# Lesson_06_2.net
KiCad netlist of a schematic drawn in Altium Designer
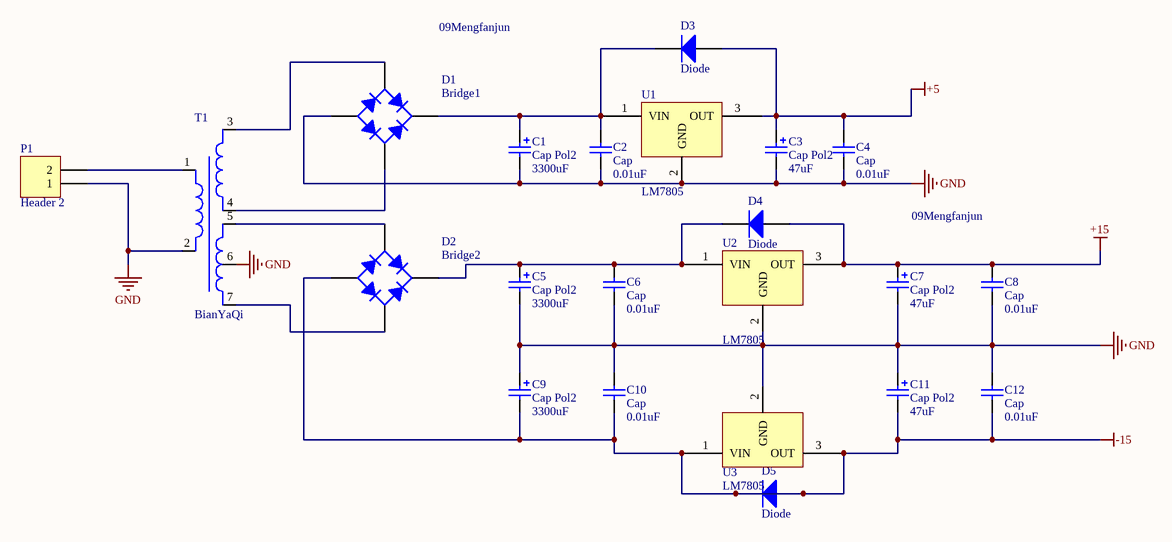
[diagram p0: Lesson_06_2.SchDoc]

(export (version "E")
  (design (tool "Eeschema 10.0.6"))
  (components
    (comp (ref "C1")
      (value "Cap Pol2")
      (footprint "POLAR0.8")
      (description "Polarized Capacitor (Axial)")
      (fields (field (name "ALTIUM_VALUE") "3300uF") (field (name "PUBLISHER") "Altium Limited"))
      (libsource (lib "Miscellaneous Devices") (part "Cap Pol2"))
    )
    (comp (ref "C2")
      (value "Cap")
      (footprint "RAD-0.3")
      (description "Capacitor")
      (fields (field (name "ALTIUM_VALUE") "0.01uF") (field (name "PUBLISHER") "Altium Limited"))
      (libsource (lib "Miscellaneous Devices") (part "Cap"))
    )
    (comp (ref "C3")
      (value "Cap Pol2")
      (footprint "POLAR0.8")
      (description "Polarized Capacitor (Axial)")
      (fields (field (name "ALTIUM_VALUE") "47uF") (field (name "PUBLISHER") "Altium Limited"))
      (libsource (lib "Miscellaneous Devices") (part "Cap Pol2"))
    )
    (comp (ref "C4")
      (value "Cap")
      (footprint "RAD-0.3")
      (description "Capacitor")
      (fields (field (name "ALTIUM_VALUE") "0.01uF") (field (name "PUBLISHER") "Altium Limited"))
      (libsource (lib "Miscellaneous Devices") (part "Cap"))
    )
    (comp (ref "C5")
      (value "Cap Pol2")
      (footprint "POLAR0.8")
      (description "Polarized Capacitor (Axial)")
      (fields (field (name "ALTIUM_VALUE") "3300uF") (field (name "PUBLISHER") "Altium Limited"))
      (libsource (lib "Miscellaneous Devices") (part "Cap Pol2"))
    )
    (comp (ref "C6")
      (value "Cap")
      (footprint "RAD-0.3")
      (description "Capacitor")
      (fields (field (name "ALTIUM_VALUE") "0.01uF") (field (name "PUBLISHER") "Altium Limited"))
      (libsource (lib "Miscellaneous Devices") (part "Cap"))
    )
    (comp (ref "C7")
      (value "Cap Pol2")
      (footprint "POLAR0.8")
      (description "Polarized Capacitor (Axial)")
      (fields (field (name "ALTIUM_VALUE") "47uF") (field (name "PUBLISHER") "Altium Limited"))
      (libsource (lib "Miscellaneous Devices") (part "Cap Pol2"))
    )
    (comp (ref "C8")
      (value "Cap")
      (footprint "RAD-0.3")
      (description "Capacitor")
      (fields (field (name "ALTIUM_VALUE") "0.01uF") (field (name "PUBLISHER") "Altium Limited"))
      (libsource (lib "Miscellaneous Devices") (part "Cap"))
    )
    (comp (ref "C9")
      (value "Cap Pol2")
      (footprint "POLAR0.8")
      (description "Polarized Capacitor (Axial)")
      (fields (field (name "ALTIUM_VALUE") "3300uF") (field (name "PUBLISHER") "Altium Limited"))
      (libsource (lib "Miscellaneous Devices") (part "Cap Pol2"))
    )
    (comp (ref "C10")
      (value "Cap")
      (footprint "RAD-0.3")
      (description "Capacitor")
      (fields (field (name "ALTIUM_VALUE") "0.01uF") (field (name "PUBLISHER") "Altium Limited"))
      (libsource (lib "Miscellaneous Devices") (part "Cap"))
    )
    (comp (ref "C11")
      (value "Cap Pol2")
      (footprint "POLAR0.8")
      (description "Polarized Capacitor (Axial)")
      (fields (field (name "ALTIUM_VALUE") "47uF") (field (name "PUBLISHER") "Altium Limited"))
      (libsource (lib "Miscellaneous Devices") (part "Cap Pol2"))
    )
    (comp (ref "C12")
      (value "Cap")
      (footprint "RAD-0.3")
      (description "Capacitor")
      (fields (field (name "ALTIUM_VALUE") "0.01uF") (field (name "PUBLISHER") "Altium Limited"))
      (libsource (lib "Miscellaneous Devices") (part "Cap"))
    )
    (comp (ref "D1")
      (value "Bridge1")
      (footprint "D-38")
      (description "Full Wave Diode Bridge")
      (fields (field (name "PUBLISHER") "Altium Limited"))
      (libsource (lib "Miscellaneous Devices") (part "Bridge1"))
    )
    (comp (ref "D2")
      (value "Bridge2")
      (footprint "D-38")
      (description "Full Wave Diode Bridge")
      (fields (field (name "PUBLISHER") "Altium Limited"))
      (libsource (lib "Miscellaneous Devices") (part "Bridge1"))
    )
    (comp (ref "D3")
      (value "Diode")
      (footprint "SMC")
      (description "Default Diode")
      (fields (field (name "PUBLISHER") "Altium Limited"))
      (libsource (lib "Miscellaneous Devices") (part "Diode"))
    )
    (comp (ref "D4")
      (value "Diode")
      (footprint "SMC")
      (description "Default Diode")
      (fields (field (name "PUBLISHER") "Altium Limited"))
      (libsource (lib "Miscellaneous Devices") (part "Diode"))
    )
    (comp (ref "D5")
      (value "Diode")
      (footprint "SMC")
      (description "Default Diode")
      (fields (field (name "PUBLISHER") "Altium Limited"))
      (libsource (lib "Miscellaneous Devices") (part "Diode"))
    )
    (comp (ref "P1")
      (value "Header 2")
      (footprint "HDR1X2")
      (description "Header, 2-Pin")
      (fields (field (name "PUBLISHER") "Altium Limited"))
      (libsource (lib "Miscellaneous Connectors") (part "Header 2"))
    )
    (comp (ref "T1")
      (value "BianYaQi")
      (footprint "PCBComponent_1")
      (libsource (lib "MIC5219") (part "BianYaQi"))
    )
    (comp (ref "U1") (value "LM7805") (footprint "LM7805") (libsource (lib "MIC5219") (part "LM7805")))
    (comp (ref "U2") (value "LM7805") (footprint "LM7805") (libsource (lib "MIC5219") (part "LM7805")))
    (comp (ref "U3") (value "LM7805") (footprint "LM7805") (libsource (lib "") (part "LM7805_1")))
  )
  (nets
    (net (code "1") (name "+5") (class "Default")
      (node (ref "C3") (pin "1") (pinfunction "1_1") (pintype "passive"))
      (node (ref "C4") (pin "2") (pinfunction "2_2") (pintype "passive"))
      (node (ref "D3") (pin "1") (pinfunction "A_1") (pintype "passive"))
      (node (ref "U1") (pin "3") (pinfunction "OUT_3") (pintype "passive"))
    )
    (net (code "2") (name "+15") (class "Default")
      (node (ref "C7") (pin "1") (pinfunction "1_1") (pintype "passive"))
      (node (ref "C8") (pin "2") (pinfunction "2_2") (pintype "passive"))
      (node (ref "D4") (pin "1") (pinfunction "A_1") (pintype "passive"))
      (node (ref "U2") (pin "3") (pinfunction "OUT_3") (pintype "passive"))
    )
    (net (code "3") (name "-15") (class "Default")
      (node (ref "C10") (pin "1") (pinfunction "1_1") (pintype "passive"))
      (node (ref "C11") (pin "2") (pinfunction "2_2") (pintype "passive"))
      (node (ref "C12") (pin "1") (pinfunction "1_1") (pintype "passive"))
      (node (ref "C9") (pin "2") (pinfunction "2_2") (pintype "passive"))
      (node (ref "D2") (pin "3") (pinfunction "A_3") (pintype "passive"))
      (node (ref "D5") (pin "1") (pinfunction "A_1") (pintype "passive"))
      (node (ref "D5") (pin "2") (pinfunction "K_2") (pintype "passive"))
      (node (ref "U3") (pin "1") (pinfunction "VIN_1") (pintype "passive"))
      (node (ref "U3") (pin "3") (pinfunction "OUT_3") (pintype "passive"))
    )
    (net (code "4") (name "GND") (class "Default")
      (node (ref "C1") (pin "2") (pinfunction "2_2") (pintype "passive"))
      (node (ref "C10") (pin "2") (pinfunction "2_2") (pintype "passive"))
      (node (ref "C11") (pin "1") (pinfunction "1_1") (pintype "passive"))
      (node (ref "C12") (pin "2") (pinfunction "2_2") (pintype "passive"))
      (node (ref "C2") (pin "1") (pinfunction "1_1") (pintype "passive"))
      (node (ref "C3") (pin "2") (pinfunction "2_2") (pintype "passive"))
      (node (ref "C4") (pin "1") (pinfunction "1_1") (pintype "passive"))
      (node (ref "C5") (pin "2") (pinfunction "2_2") (pintype "passive"))
      (node (ref "C6") (pin "1") (pinfunction "1_1") (pintype "passive"))
      (node (ref "C7") (pin "2") (pinfunction "2_2") (pintype "passive"))
      (node (ref "C8") (pin "1") (pinfunction "1_1") (pintype "passive"))
      (node (ref "C9") (pin "1") (pinfunction "1_1") (pintype "passive"))
      (node (ref "D1") (pin "3") (pinfunction "A_3") (pintype "passive"))
      (node (ref "P1") (pin "1") (pinfunction "1_1") (pintype "passive"))
      (node (ref "T1") (pin "2") (pinfunction "Pri-_2") (pintype "passive"))
      (node (ref "T1") (pin "6") (pinfunction "6_6") (pintype "passive"))
      (node (ref "U1") (pin "2") (pinfunction "GND_2") (pintype "passive"))
      (node (ref "U2") (pin "2") (pinfunction "GND_2") (pintype "passive"))
      (node (ref "U3") (pin "2") (pinfunction "GND_2") (pintype "passive"))
    )
    (net (code "5") (name "Net-(D1-K)") (class "Default")
      (node (ref "C1") (pin "1") (pinfunction "1_1") (pintype "passive"))
      (node (ref "C2") (pin "2") (pinfunction "2_2") (pintype "passive"))
      (node (ref "D1") (pin "1") (pinfunction "K_1") (pintype "passive"))
      (node (ref "D3") (pin "2") (pinfunction "K_2") (pintype "passive"))
      (node (ref "U1") (pin "1") (pinfunction "VIN_1") (pintype "passive"))
    )
    (net (code "6") (name "Net-(D2-K)") (class "Default")
      (node (ref "C5") (pin "1") (pinfunction "1_1") (pintype "passive"))
      (node (ref "C6") (pin "2") (pinfunction "2_2") (pintype "passive"))
      (node (ref "D2") (pin "1") (pinfunction "K_1") (pintype "passive"))
      (node (ref "D4") (pin "2") (pinfunction "K_2") (pintype "passive"))
      (node (ref "U2") (pin "1") (pinfunction "VIN_1") (pintype "passive"))
    )
    (net (code "7") (name "Net-(T1-Pri+)") (class "Default")
      (node (ref "P1") (pin "2") (pinfunction "2_2") (pintype "passive"))
      (node (ref "T1") (pin "1") (pinfunction "Pri+_1") (pintype "passive"))
    )
    (net (code "8") (name "Net-(T1-Sec1+)") (class "Default")
      (node (ref "D1") (pin "4") (pinfunction "C_4") (pintype "passive"))
      (node (ref "T1") (pin "3") (pinfunction "Sec1+_3") (pintype "passive"))
    )
    (net (code "9") (name "Net-(T1-Sec1-)") (class "Default")
      (node (ref "D1") (pin "2") (pinfunction "C_2") (pintype "passive"))
      (node (ref "T1") (pin "4") (pinfunction "Sec1-_4") (pintype "passive"))
    )
    (net (code "10") (name "Net-(T1-Sec2+)") (class "Default")
      (node (ref "D2") (pin "4") (pinfunction "C_4") (pintype "passive"))
      (node (ref "T1") (pin "5") (pinfunction "Sec2+_5") (pintype "passive"))
    )
    (net (code "11") (name "Net-(T1-Sec2-)") (class "Default")
      (node (ref "D2") (pin "2") (pinfunction "C_2") (pintype "passive"))
      (node (ref "T1") (pin "7") (pinfunction "Sec2-_7") (pintype "passive"))
    )
  )
)
